# DriverPCB.net
KiCad netlist of a schematic drawn in Altium Designer
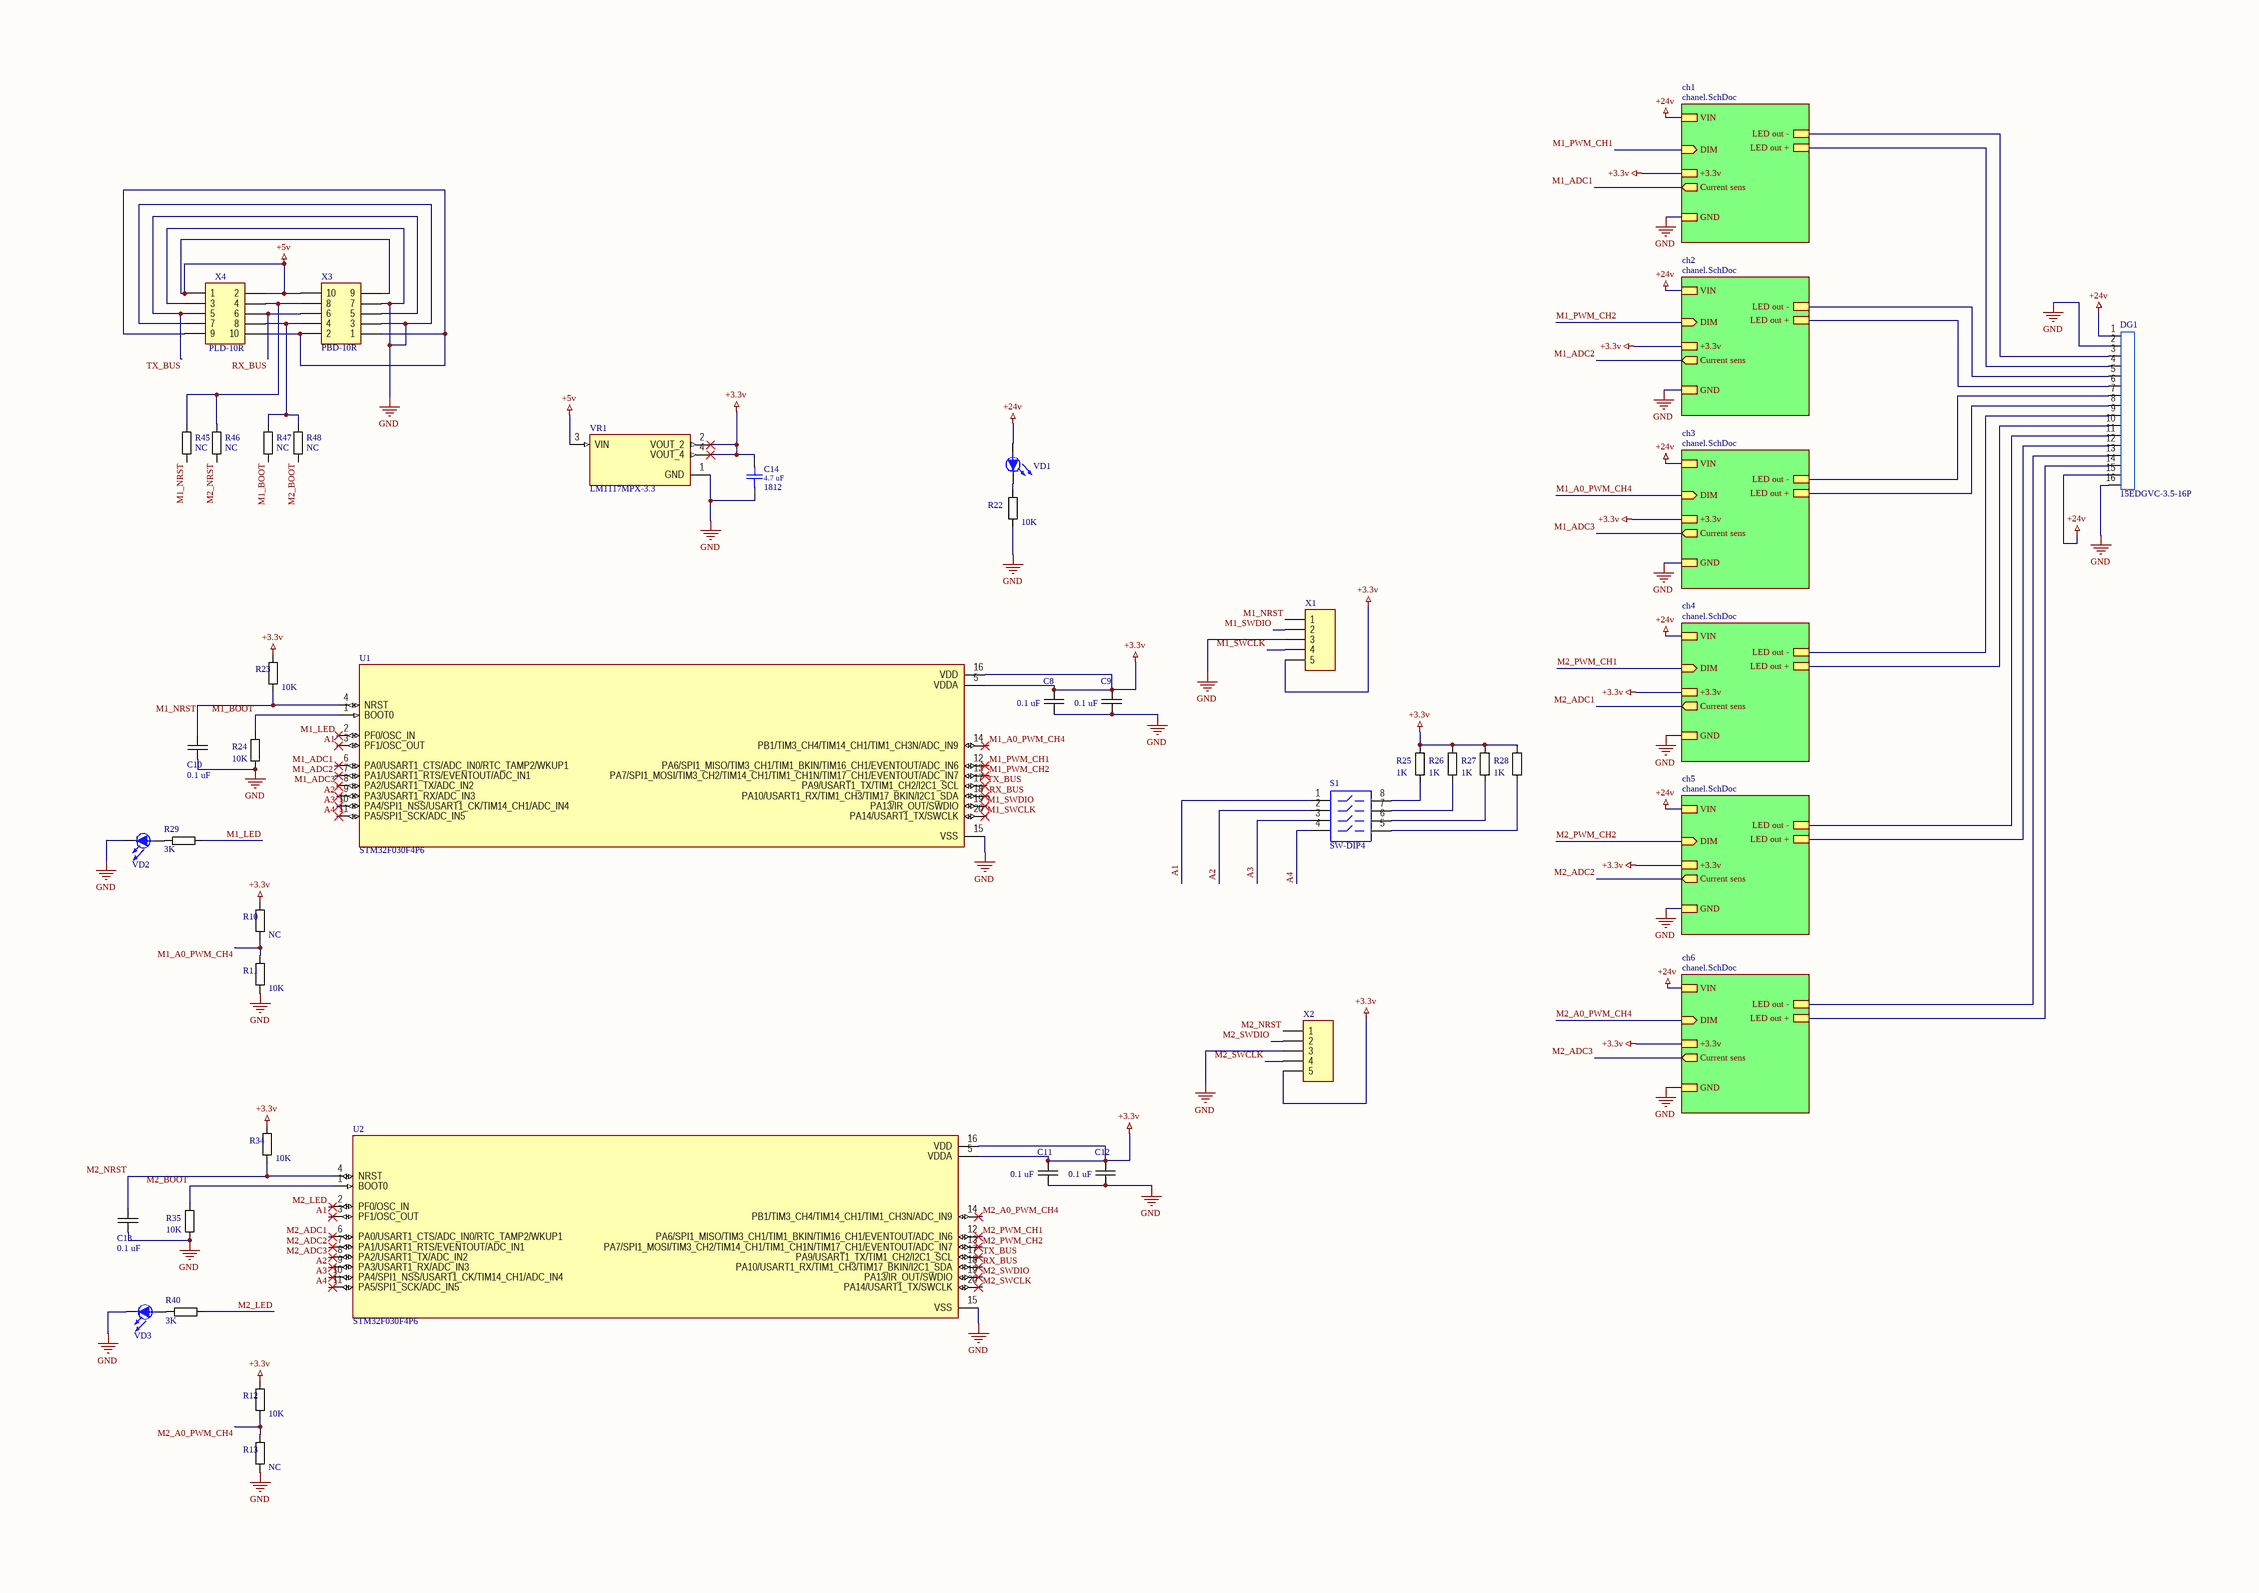
[diagram p0: DriverPCB.SchDoc]

(export (version "E")
  (design (tool "Eeschema 10.0.6"))
  (components
    (comp (ref "C8")
      (value "0.1 uF")
      (footprint "CAPACITOR 0603")
      (libsource (lib "Maks_lib") (part "Capasitor"))
    )
    (comp (ref "C9")
      (value "0.1 uF")
      (footprint "CAPACITOR 0603")
      (libsource (lib "Maks_lib") (part "Capasitor"))
    )
    (comp (ref "C10")
      (value "0.1 uF")
      (footprint "CAPACITOR 0603")
      (libsource (lib "Maks_lib") (part "Capasitor"))
    )
    (comp (ref "C11")
      (value "0.1 uF")
      (footprint "CAPACITOR 0603")
      (libsource (lib "Maks_lib") (part "Capasitor"))
    )
    (comp (ref "C12")
      (value "0.1 uF")
      (footprint "CAPACITOR 0603")
      (libsource (lib "Maks_lib") (part "Capasitor"))
    )
    (comp (ref "C13")
      (value "0.1 uF")
      (footprint "CAPACITOR 0603")
      (libsource (lib "Maks_lib") (part "Capasitor"))
    )
    (comp (ref "C14")
      (value "4.7 uF")
      (footprint "CAPCHIP1812")
      (description "Ceramic Capacitor")
      (fields (field (name "PACKAGE") "1812") (field (name "Comment") "Cap C"))
      (libsource (lib "RCL") (part "Cap C"))
    )
    (comp (ref "DG1")
      (value "15EDGVC-3.5-16P")
      (footprint "15EDGVC-3.5-16P")
      (libsource (lib "Degson") (part "15EDGVC-3.5-16P"))
    )
    (comp (ref "R10") (value "NC") (footprint "Resistor 0402") (libsource (lib "Maks_lib") (part "Resistor")))
    (comp (ref "R11")
      (value "10K")
      (footprint "Resistor 0402")
      (libsource (lib "Maks_lib") (part "Resistor"))
    )
    (comp (ref "R12")
      (value "10K")
      (footprint "Resistor 0402")
      (libsource (lib "Maks_lib") (part "Resistor"))
    )
    (comp (ref "R13") (value "NC") (footprint "Resistor 0402") (libsource (lib "Maks_lib") (part "Resistor")))
    (comp (ref "R22")
      (value "10K")
      (footprint "Resistor 0402")
      (libsource (lib "Maks_lib") (part "Resistor"))
    )
    (comp (ref "R23")
      (value "10K")
      (footprint "Resistor 0402")
      (libsource (lib "Maks_lib") (part "Resistor"))
    )
    (comp (ref "R24")
      (value "10K")
      (footprint "Resistor 0402")
      (libsource (lib "Maks_lib") (part "Resistor"))
    )
    (comp (ref "R25") (value "1K") (footprint "Resistor 0402") (libsource (lib "Maks_lib") (part "Resistor")))
    (comp (ref "R26") (value "1K") (footprint "Resistor 0402") (libsource (lib "Maks_lib") (part "Resistor")))
    (comp (ref "R27") (value "1K") (footprint "Resistor 0402") (libsource (lib "Maks_lib") (part "Resistor")))
    (comp (ref "R28") (value "1K") (footprint "Resistor 0402") (libsource (lib "Maks_lib") (part "Resistor")))
    (comp (ref "R29") (value "3K") (footprint "Resistor 0402") (libsource (lib "Maks_lib") (part "Resistor")))
    (comp (ref "R34")
      (value "10K")
      (footprint "Resistor 0402")
      (libsource (lib "Maks_lib") (part "Resistor"))
    )
    (comp (ref "R35")
      (value "10K")
      (footprint "Resistor 0402")
      (libsource (lib "Maks_lib") (part "Resistor"))
    )
    (comp (ref "R40") (value "3K") (footprint "Resistor 0402") (libsource (lib "Maks_lib") (part "Resistor")))
    (comp (ref "R45") (value "NC") (footprint "Resistor 0402") (libsource (lib "Maks_lib") (part "Resistor")))
    (comp (ref "R46") (value "NC") (footprint "Resistor 0402") (libsource (lib "Maks_lib") (part "Resistor")))
    (comp (ref "R47") (value "NC") (footprint "Resistor 0402") (libsource (lib "Maks_lib") (part "Resistor")))
    (comp (ref "R48") (value "NC") (footprint "Resistor 0402") (libsource (lib "Maks_lib") (part "Resistor")))
    (comp (ref "S1")
      (value "SW-DIP4")
      (footprint "DIP-8")
      (description "DIP Switch")
      (fields (field (name "PUBLISHER") "Altium Limited"))
      (libsource (lib "Miscellaneous Devices") (part "SW-DIP4"))
    )
    (comp (ref "U1")
      (value "STM32F030F4P6")
      (footprint "SOP65P640X120-20N")
      (description "MCU 32-bit STM32F ARM Cortex M0 RISC 16KB Flash 2.5V/3.3V 20-Pin TSSOP Tray")
      (libsource (lib "STM32F030F4P6") (part "STM32F030F4P6"))
    )
    (comp (ref "U2")
      (value "STM32F030F4P6")
      (footprint "SOP65P640X120-20N")
      (description "MCU 32-bit STM32F ARM Cortex M0 RISC 16KB Flash 2.5V/3.3V 20-Pin TSSOP Tray")
      (libsource (lib "STM32F030F4P6") (part "STM32F030F4P6"))
    )
    (comp (ref "VD1") (value "one color") (footprint "0805-") (libsource (lib "DT") (part "LED SMD")))
    (comp (ref "VD2") (value "~") (footprint "0805-") (libsource (lib "DT") (part "LED SMD")))
    (comp (ref "VD3") (value "~") (footprint "0805-") (libsource (lib "DT") (part "LED SMD")))
    (comp (ref "VR1")
      (value "LM1117MPX-3.3")
      (footprint "VREG_LM1117MPX-3.3")
      (description "800-mA 15-V linear voltage regulator")
      (fields (field (name "MF") "Texas Instruments"))
      (libsource (lib "LM1117MPX-3.3") (part "LM1117MPX-3.3"))
    )
    (comp (ref "X1")
      (value "~")
      (footprint "PLS-5-3D")
      (description "Header, 5-Pin")
      (fields (field (name "PARTNUMBER") "PLS-5"))
      (libsource (lib "AX_Altium_v2.3") (part "PLS-5"))
    )
    (comp (ref "X2")
      (value "~")
      (footprint "PLS-5-3D")
      (description "Header, 5-Pin")
      (fields (field (name "PARTNUMBER") "PLS-5"))
      (libsource (lib "AX_Altium_v2.3") (part "PLS-5"))
    )
    (comp (ref "X3")
      (value "PBD-10R")
      (footprint "PBD-10RR")
      (description "Header, 5-Pin, Dual row")
      (libsource (lib "AX_Altium_v2.3") (part "PBD-10R"))
    )
    (comp (ref "X4")
      (value "PLD-10R")
      (footprint "PLD-10RR2")
      (description "Header, 5-Pin, Dual row")
      (libsource (lib "AX_Altium_v2.3") (part "PLD-10R"))
    )
  )
  (nets
    (net (code "1") (name "+3.3v") (class "Default")
      (node (ref "C11") (pin "1") (pinfunction "1_1") (pintype "passive"))
      (node (ref "C12") (pin "1") (pinfunction "1_1") (pintype "passive"))
      (node (ref "C14") (pin "2") (pinfunction "2_2") (pintype "passive"))
      (node (ref "C8") (pin "1") (pinfunction "1_1") (pintype "passive"))
      (node (ref "C9") (pin "1") (pinfunction "1_1") (pintype "passive"))
      (node (ref "R10") (pin "2") (pinfunction "2_2") (pintype "passive"))
      (node (ref "R12") (pin "2") (pinfunction "2_2") (pintype "passive"))
      (node (ref "R23") (pin "2") (pinfunction "2_2") (pintype "passive"))
      (node (ref "R25") (pin "1") (pinfunction "1_1") (pintype "passive"))
      (node (ref "R26") (pin "1") (pinfunction "1_1") (pintype "passive"))
      (node (ref "R27") (pin "1") (pinfunction "1_1") (pintype "passive"))
      (node (ref "R28") (pin "1") (pinfunction "1_1") (pintype "passive"))
      (node (ref "R34") (pin "2") (pinfunction "2_2") (pintype "passive"))
      (node (ref "U1") (pin "16") (pinfunction "VDD_16") (pintype "power_in"))
      (node (ref "U1") (pin "5") (pinfunction "VDDA_5") (pintype "power_in"))
      (node (ref "U2") (pin "16") (pinfunction "VDD_16") (pintype "power_in"))
      (node (ref "U2") (pin "5") (pinfunction "VDDA_5") (pintype "power_in"))
      (node (ref "VR1") (pin "2") (pinfunction "VOUT_2_2") (pintype "output"))
      (node (ref "VR1") (pin "4") (pinfunction "VOUT_4_4") (pintype "output"))
      (node (ref "X1") (pin "5") (pinfunction "5_5") (pintype "passive"))
      (node (ref "X2") (pin "5") (pinfunction "5_5") (pintype "passive"))
    )
    (net (code "2") (name "+5v") (class "Default")
      (node (ref "VR1") (pin "3") (pinfunction "VIN_3") (pintype "input"))
      (node (ref "X3") (pin "10") (pinfunction "10_10") (pintype "passive"))
      (node (ref "X3") (pin "9") (pinfunction "9_9") (pintype "passive"))
      (node (ref "X4") (pin "1") (pinfunction "1_1") (pintype "passive"))
      (node (ref "X4") (pin "2") (pinfunction "2_2") (pintype "passive"))
    )
    (net (code "3") (name "+24v") (class "Default")
      (node (ref "DG1") (pin "1") (pintype "passive"))
      (node (ref "DG1") (pin "15") (pintype "passive"))
      (node (ref "VD1") (pin "A") (pinfunction "a_A") (pintype "passive"))
    )
    (net (code "4") (name "/A1") (class "Default")
      (node (ref "S1") (pin "1") (pinfunction "1_1") (pintype "passive"))
      (node (ref "U1") (pin "3") (pinfunction "PF1/OSC_OUT_3") (pintype "bidirectional"))
      (node (ref "U2") (pin "3") (pinfunction "PF1/OSC_OUT_3") (pintype "bidirectional"))
    )
    (net (code "5") (name "/A2") (class "Default")
      (node (ref "S1") (pin "2") (pinfunction "2_2") (pintype "passive"))
      (node (ref "U1") (pin "9") (pinfunction "PA3/USART1_RX/ADC_IN3_9") (pintype "bidirectional"))
      (node (ref "U2") (pin "9") (pinfunction "PA3/USART1_RX/ADC_IN3_9") (pintype "bidirectional"))
    )
    (net (code "6") (name "/A3") (class "Default")
      (node (ref "S1") (pin "3") (pinfunction "3_3") (pintype "passive"))
      (node (ref "U1") (pin "10") (pinfunction "PA4/SPI1_NSS/USART1_CK/TIM14_CH1/ADC_IN4_10") (pintype "bidirectional"))
      (node (ref "U2") (pin "10") (pinfunction "PA4/SPI1_NSS/USART1_CK/TIM14_CH1/ADC_IN4_10") (pintype "bidirectional"))
    )
    (net (code "7") (name "/A4") (class "Default")
      (node (ref "S1") (pin "4") (pinfunction "4_4") (pintype "passive"))
      (node (ref "U1") (pin "11") (pinfunction "PA5/SPI1_SCK/ADC_IN5_11") (pintype "bidirectional"))
      (node (ref "U2") (pin "11") (pinfunction "PA5/SPI1_SCK/ADC_IN5_11") (pintype "bidirectional"))
    )
    (net (code "10") (name "/LED out +") (class "Default") (node (ref "DG1") (pin "12") (pintype "passive")))
    (net (code "11") (name "/LED out +_1") (class "Default") (node (ref "DG1") (pin "4") (pintype "passive")))
    (net (code "12") (name "/LED out +_2") (class "Default") (node (ref "DG1") (pin "6") (pintype "passive")))
    (net (code "13") (name "/LED out +_3") (class "Default")
      (node (ref "DG1") (pin "14") (pintype "passive"))
    )
    (net (code "14") (name "/LED out +_4") (class "Default") (node (ref "DG1") (pin "8") (pintype "passive")))
    (net (code "15") (name "/LED out +_5") (class "Default")
      (node (ref "DG1") (pin "10") (pintype "passive"))
    )
    (net (code "16") (name "/LED out -") (class "Default") (node (ref "DG1") (pin "11") (pintype "passive")))
    (net (code "17") (name "/LED out -_1") (class "Default") (node (ref "DG1") (pin "3") (pintype "passive")))
    (net (code "18") (name "/LED out -_2") (class "Default") (node (ref "DG1") (pin "5") (pintype "passive")))
    (net (code "19") (name "/LED out -_3") (class "Default")
      (node (ref "DG1") (pin "13") (pintype "passive"))
    )
    (net (code "20") (name "/LED out -_4") (class "Default") (node (ref "DG1") (pin "7") (pintype "passive")))
    (net (code "21") (name "/LED out -_5") (class "Default") (node (ref "DG1") (pin "9") (pintype "passive")))
    (net (code "22") (name "/M1_A0_PWM_CH4") (class "Default")
      (node (ref "R10") (pin "1") (pinfunction "1_1") (pintype "passive"))
      (node (ref "R11") (pin "2") (pinfunction "2_2") (pintype "passive"))
      (node (ref "U1") (pin "14") (pinfunction "PB1/TIM3_CH4/TIM14_CH1/TIM1_CH3N/ADC_IN9_14") (pintype "bidirectional"))
    )
    (net (code "23") (name "/M1_ADC1") (class "Default")
      (node (ref "U1") (pin "6") (pinfunction "PA0/USART1_CTS/ADC_IN0/RTC_TAMP2/WKUP1_6") (pintype "bidirectional+no_connect"))
    )
    (net (code "24") (name "/M1_ADC2") (class "Default")
      (node (ref "U1") (pin "7") (pinfunction "PA1/USART1_RTS/EVENTOUT/ADC_IN1_7") (pintype "bidirectional+no_connect"))
    )
    (net (code "25") (name "/M1_ADC3") (class "Default")
      (node (ref "U1") (pin "8") (pinfunction "PA2/USART1_TX/ADC_IN2_8") (pintype "bidirectional+no_connect"))
    )
    (net (code "26") (name "/M1_BOOT") (class "Default")
      (node (ref "R24") (pin "1") (pinfunction "1_1") (pintype "passive"))
      (node (ref "R47") (pin "2") (pinfunction "2_2") (pintype "passive"))
      (node (ref "U1") (pin "1") (pinfunction "BOOT0_1") (pintype "input"))
    )
    (net (code "27") (name "/M1_LED") (class "Default")
      (node (ref "R29") (pin "1") (pinfunction "1_1") (pintype "passive"))
      (node (ref "U1") (pin "2") (pinfunction "PF0/OSC_IN_2") (pintype "bidirectional"))
    )
    (net (code "28") (name "/M1_NRST") (class "Default")
      (node (ref "C10") (pin "2") (pinfunction "2_2") (pintype "passive"))
      (node (ref "R23") (pin "1") (pinfunction "1_1") (pintype "passive"))
      (node (ref "R45") (pin "2") (pinfunction "2_2") (pintype "passive"))
      (node (ref "U1") (pin "4") (pinfunction "NRST_4") (pintype "bidirectional"))
      (node (ref "X1") (pin "1") (pinfunction "1_1") (pintype "passive"))
    )
    (net (code "29") (name "/M1_PWM_CH1") (class "Default")
      (node (ref "U1") (pin "12") (pinfunction "PA6/SPI1_MISO/TIM3_CH1/TIM1_BKIN/TIM16_CH1/EVENTOUT/ADC_IN6_12") (pintype "bidirectional+no_connect"))
    )
    (net (code "30") (name "/M1_PWM_CH2") (class "Default")
      (node (ref "U1") (pin "13") (pinfunction "PA7/SPI1_MOSI/TIM3_CH2/TIM14_CH1/TIM1_CH1N/TIM17_CH1/EVENTOUT/ADC_IN7_13") (pintype "bidirectional+no_connect"))
    )
    (net (code "31") (name "/M1_SWCLK") (class "Default")
      (node (ref "U1") (pin "20") (pinfunction "PA14/USART1_TX/SWCLK_20") (pintype "bidirectional"))
      (node (ref "X1") (pin "4") (pinfunction "4_4") (pintype "passive"))
    )
    (net (code "32") (name "/M1_SWDIO") (class "Default")
      (node (ref "U1") (pin "19") (pinfunction "PA13/IR_OUT/SWDIO_19") (pintype "bidirectional"))
      (node (ref "X1") (pin "2") (pinfunction "2_2") (pintype "passive"))
    )
    (net (code "33") (name "/M2_A0_PWM_CH4") (class "Default")
      (node (ref "R12") (pin "1") (pinfunction "1_1") (pintype "passive"))
      (node (ref "R13") (pin "2") (pinfunction "2_2") (pintype "passive"))
      (node (ref "U2") (pin "14") (pinfunction "PB1/TIM3_CH4/TIM14_CH1/TIM1_CH3N/ADC_IN9_14") (pintype "bidirectional"))
    )
    (net (code "34") (name "/M2_ADC1") (class "Default")
      (node (ref "U2") (pin "6") (pinfunction "PA0/USART1_CTS/ADC_IN0/RTC_TAMP2/WKUP1_6") (pintype "bidirectional+no_connect"))
    )
    (net (code "35") (name "/M2_ADC2") (class "Default")
      (node (ref "U2") (pin "7") (pinfunction "PA1/USART1_RTS/EVENTOUT/ADC_IN1_7") (pintype "bidirectional+no_connect"))
    )
    (net (code "36") (name "/M2_ADC3") (class "Default")
      (node (ref "U2") (pin "8") (pinfunction "PA2/USART1_TX/ADC_IN2_8") (pintype "bidirectional+no_connect"))
    )
    (net (code "37") (name "/M2_BOOT") (class "Default")
      (node (ref "R35") (pin "1") (pinfunction "1_1") (pintype "passive"))
      (node (ref "R48") (pin "2") (pinfunction "2_2") (pintype "passive"))
      (node (ref "U2") (pin "1") (pinfunction "BOOT0_1") (pintype "input"))
    )
    (net (code "38") (name "/M2_LED") (class "Default")
      (node (ref "R40") (pin "1") (pinfunction "1_1") (pintype "passive"))
      (node (ref "U2") (pin "2") (pinfunction "PF0/OSC_IN_2") (pintype "bidirectional"))
    )
    (net (code "39") (name "/M2_NRST") (class "Default")
      (node (ref "C13") (pin "2") (pinfunction "2_2") (pintype "passive"))
      (node (ref "R34") (pin "1") (pinfunction "1_1") (pintype "passive"))
      (node (ref "R46") (pin "2") (pinfunction "2_2") (pintype "passive"))
      (node (ref "U2") (pin "4") (pinfunction "NRST_4") (pintype "bidirectional"))
      (node (ref "X2") (pin "1") (pinfunction "1_1") (pintype "passive"))
    )
    (net (code "40") (name "/M2_PWM_CH1") (class "Default")
      (node (ref "U2") (pin "12") (pinfunction "PA6/SPI1_MISO/TIM3_CH1/TIM1_BKIN/TIM16_CH1/EVENTOUT/ADC_IN6_12") (pintype "bidirectional+no_connect"))
    )
    (net (code "41") (name "/M2_PWM_CH2") (class "Default")
      (node (ref "U2") (pin "13") (pinfunction "PA7/SPI1_MOSI/TIM3_CH2/TIM14_CH1/TIM1_CH1N/TIM17_CH1/EVENTOUT/ADC_IN7_13") (pintype "bidirectional+no_connect"))
    )
    (net (code "42") (name "/M2_SWCLK") (class "Default")
      (node (ref "U2") (pin "20") (pinfunction "PA14/USART1_TX/SWCLK_20") (pintype "bidirectional"))
      (node (ref "X2") (pin "4") (pinfunction "4_4") (pintype "passive"))
    )
    (net (code "43") (name "/M2_SWDIO") (class "Default")
      (node (ref "U2") (pin "19") (pinfunction "PA13/IR_OUT/SWDIO_19") (pintype "bidirectional"))
      (node (ref "X2") (pin "2") (pinfunction "2_2") (pintype "passive"))
    )
    (net (code "44") (name "/RX_BUS") (class "Default")
      (node (ref "U1") (pin "18") (pinfunction "PA10/USART1_RX/TIM1_CH3/TIM17_BKIN/I2C1_SDA_18") (pintype "bidirectional"))
      (node (ref "U2") (pin "18") (pinfunction "PA10/USART1_RX/TIM1_CH3/TIM17_BKIN/I2C1_SDA_18") (pintype "bidirectional"))
      (node (ref "X3") (pin "6") (pinfunction "6_6") (pintype "passive"))
      (node (ref "X4") (pin "6") (pinfunction "6_6") (pintype "passive"))
    )
    (net (code "45") (name "/TX_BUS") (class "Default")
      (node (ref "U1") (pin "17") (pinfunction "PA9/USART1_TX/TIM1_CH2/I2C1_SCL_17") (pintype "bidirectional"))
      (node (ref "U2") (pin "17") (pinfunction "PA9/USART1_TX/TIM1_CH2/I2C1_SCL_17") (pintype "bidirectional"))
      (node (ref "X3") (pin "5") (pinfunction "5_5") (pintype "passive"))
      (node (ref "X4") (pin "5") (pinfunction "5_5") (pintype "passive"))
    )
    (net (code "46") (name "GND") (class "Default")
      (node (ref "C10") (pin "1") (pinfunction "1_1") (pintype "passive"))
      (node (ref "C11") (pin "2") (pinfunction "2_2") (pintype "passive"))
      (node (ref "C12") (pin "2") (pinfunction "2_2") (pintype "passive"))
      (node (ref "C13") (pin "1") (pinfunction "1_1") (pintype "passive"))
      (node (ref "C14") (pin "1") (pinfunction "1_1") (pintype "passive"))
      (node (ref "C8") (pin "2") (pinfunction "2_2") (pintype "passive"))
      (node (ref "C9") (pin "2") (pinfunction "2_2") (pintype "passive"))
      (node (ref "DG1") (pin "16") (pintype "passive"))
      (node (ref "DG1") (pin "2") (pintype "passive"))
      (node (ref "R11") (pin "1") (pinfunction "1_1") (pintype "passive"))
      (node (ref "R13") (pin "1") (pinfunction "1_1") (pintype "passive"))
      (node (ref "R22") (pin "1") (pinfunction "1_1") (pintype "passive"))
      (node (ref "R24") (pin "2") (pinfunction "2_2") (pintype "passive"))
      (node (ref "R35") (pin "2") (pinfunction "2_2") (pintype "passive"))
      (node (ref "U1") (pin "15") (pinfunction "VSS_15") (pintype "power_in"))
      (node (ref "U2") (pin "15") (pinfunction "VSS_15") (pintype "power_in"))
      (node (ref "VD2") (pin "K") (pinfunction "k_K") (pintype "passive"))
      (node (ref "VD3") (pin "K") (pinfunction "k_K") (pintype "passive"))
      (node (ref "VR1") (pin "1") (pinfunction "GND_1") (pintype "power_in"))
      (node (ref "X1") (pin "3") (pinfunction "3_3") (pintype "passive"))
      (node (ref "X2") (pin "3") (pinfunction "3_3") (pintype "passive"))
      (node (ref "X3") (pin "3") (pinfunction "3_3") (pintype "passive"))
      (node (ref "X3") (pin "7") (pinfunction "7_7") (pintype "passive"))
      (node (ref "X4") (pin "3") (pinfunction "3_3") (pintype "passive"))
      (node (ref "X4") (pin "7") (pinfunction "7_7") (pintype "passive"))
    )
    (net (code "47") (name "Net-(R25-Pad2)") (class "Default")
      (node (ref "R25") (pin "2") (pinfunction "2_2") (pintype "passive"))
      (node (ref "S1") (pin "8") (pinfunction "8_8") (pintype "passive"))
    )
    (net (code "48") (name "Net-(R26-Pad2)") (class "Default")
      (node (ref "R26") (pin "2") (pinfunction "2_2") (pintype "passive"))
      (node (ref "S1") (pin "7") (pinfunction "7_7") (pintype "passive"))
    )
    (net (code "49") (name "Net-(R27-Pad2)") (class "Default")
      (node (ref "R27") (pin "2") (pinfunction "2_2") (pintype "passive"))
      (node (ref "S1") (pin "6") (pinfunction "6_6") (pintype "passive"))
    )
    (net (code "50") (name "Net-(R28-Pad2)") (class "Default")
      (node (ref "R28") (pin "2") (pinfunction "2_2") (pintype "passive"))
      (node (ref "S1") (pin "5") (pinfunction "5_5") (pintype "passive"))
    )
    (net (code "51") (name "Net-(R45-Pad1)") (class "Default")
      (node (ref "R45") (pin "1") (pinfunction "1_1") (pintype "passive"))
      (node (ref "R46") (pin "1") (pinfunction "1_1") (pintype "passive"))
      (node (ref "X3") (pin "8") (pinfunction "8_8") (pintype "passive"))
      (node (ref "X4") (pin "4") (pinfunction "4_4") (pintype "passive"))
    )
    (net (code "52") (name "Net-(R47-Pad1)") (class "Default")
      (node (ref "R47") (pin "1") (pinfunction "1_1") (pintype "passive"))
      (node (ref "R48") (pin "1") (pinfunction "1_1") (pintype "passive"))
      (node (ref "X3") (pin "4") (pinfunction "4_4") (pintype "passive"))
      (node (ref "X4") (pin "8") (pinfunction "8_8") (pintype "passive"))
    )
    (net (code "53") (name "Net-(VD1-k)") (class "Default")
      (node (ref "R22") (pin "2") (pinfunction "2_2") (pintype "passive"))
      (node (ref "VD1") (pin "K") (pinfunction "k_K") (pintype "passive"))
    )
    (net (code "54") (name "Net-(VD2-a)") (class "Default")
      (node (ref "R29") (pin "2") (pinfunction "2_2") (pintype "passive"))
      (node (ref "VD2") (pin "A") (pinfunction "a_A") (pintype "passive"))
    )
    (net (code "55") (name "Net-(VD3-a)") (class "Default")
      (node (ref "R40") (pin "2") (pinfunction "2_2") (pintype "passive"))
      (node (ref "VD3") (pin "A") (pinfunction "a_A") (pintype "passive"))
    )
    (net (code "56") (name "Net-(X3-Pad1)") (class "Default")
      (node (ref "X3") (pin "1") (pinfunction "1_1") (pintype "passive"))
      (node (ref "X3") (pin "2") (pinfunction "2_2") (pintype "passive"))
      (node (ref "X4") (pin "10") (pinfunction "10_10") (pintype "passive"))
      (node (ref "X4") (pin "9") (pinfunction "9_9") (pintype "passive"))
    )
  )
)
